# PK_MUV.net
KiCad netlist of a schematic drawn in EAGLE
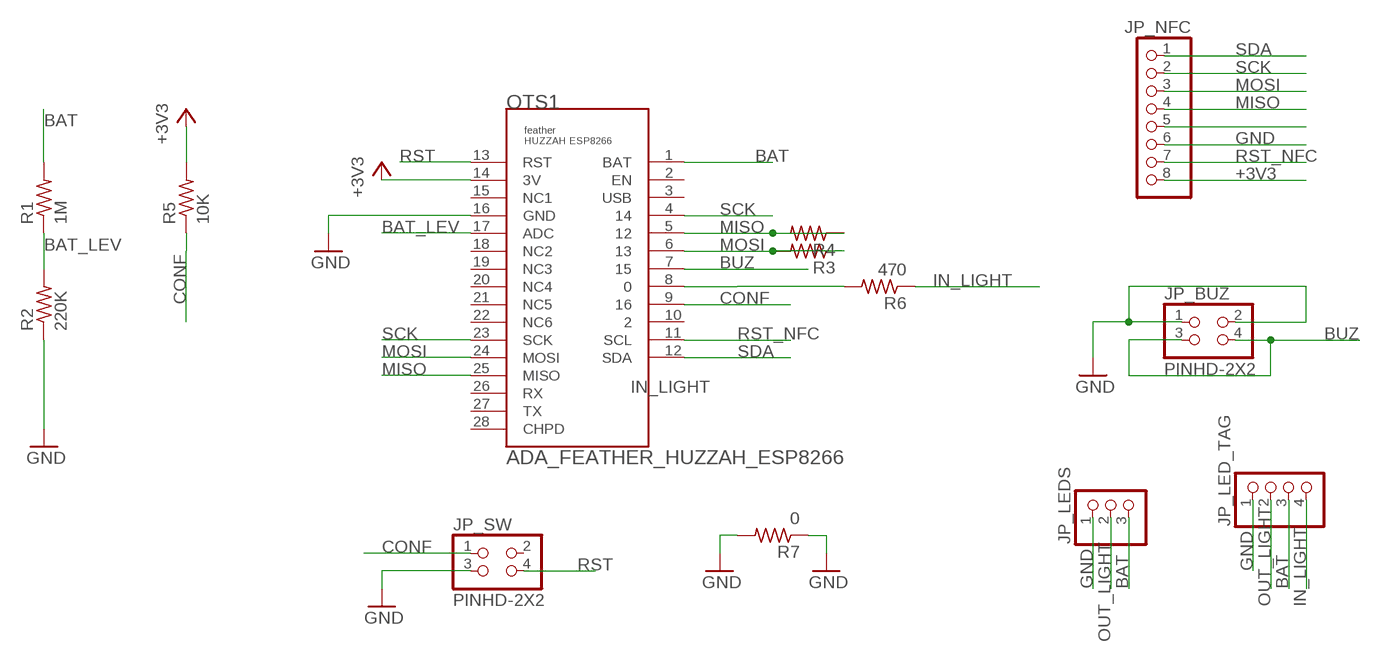
[diagram p0: schematic, sheet 1]

(export (version "E")
  (design (tool "Eeschema 10.0.6"))
  (components
    (comp (ref "JP_BUZ")
      (value "PINHD-2X2")
      (footprint "eagle-import:2X2")
      (libsource (lib "eagle-import") (part "PINHD-2X2"))
    )
    (comp (ref "JP_LEDS")
      (value "HEADER-1X3")
      (footprint "eagle-import:1X03_OVAL")
      (libsource (lib "eagle-import") (part "HEADER-1X3"))
    )
    (comp (ref "JP_LED_TAG")
      (value "HEADER-1X4")
      (footprint "eagle-import:1X04_OVAL")
      (libsource (lib "eagle-import") (part "HEADER-1X4"))
    )
    (comp (ref "JP_NFC")
      (value "HEADER-1X8")
      (footprint "eagle-import:1X08_OVAL")
      (libsource (lib "eagle-import") (part "HEADER-1X8"))
    )
    (comp (ref "JP_SW")
      (value "PINHD-2X2")
      (footprint "eagle-import:2X2")
      (libsource (lib "eagle-import") (part "PINHD-2X2"))
    )
    (comp (ref "OTS1")
      (value "ADA_FEATHER_HUZZAH_ESP8266")
      (footprint "eagle-import:ADA_FEATHER_HUZZAH_ESP8266")
      (libsource (lib "eagle-import") (part "ADA_FEATHER_HUZZAH_ESP8266"))
    )
    (comp (ref "R1")
      (value "1M")
      (footprint "eagle-import:M1206")
      (libsource (lib "eagle-import") (part "R-US_M1206"))
    )
    (comp (ref "R2")
      (value "220K")
      (footprint "eagle-import:M1206")
      (libsource (lib "eagle-import") (part "R-US_M1206"))
    )
    (comp (ref "R3")
      (value "R-US_M1206")
      (footprint "eagle-import:M1206")
      (libsource (lib "eagle-import") (part "R-US_M1206"))
    )
    (comp (ref "R4")
      (value "R-US_M1206")
      (footprint "eagle-import:M1206")
      (libsource (lib "eagle-import") (part "R-US_M1206"))
    )
    (comp (ref "R5")
      (value "10K")
      (footprint "eagle-import:M1206")
      (libsource (lib "eagle-import") (part "R-US_M1206"))
    )
    (comp (ref "R6")
      (value "470")
      (footprint "eagle-import:M1206")
      (libsource (lib "eagle-import") (part "R-US_M1206"))
    )
    (comp (ref "R7")
      (value "0")
      (footprint "eagle-import:M1206")
      (libsource (lib "eagle-import") (part "R-US_M1206"))
    )
  )
  (nets
    (net (code "1") (name "+3V3") (class "Default")
      (node (ref "JP_NFC") (pin "8") (pinfunction "8_8") (pintype "passive"))
      (node (ref "OTS1") (pin "14") (pinfunction "3V_14") (pintype "power_in"))
      (node (ref "R5") (pin "2") (pinfunction "2_2") (pintype "passive"))
    )
    (net (code "2") (name "/BAT") (class "Default")
      (node (ref "JP_LEDS") (pin "3") (pinfunction "3_3") (pintype "passive"))
      (node (ref "JP_LED_TAG") (pin "3") (pinfunction "3_3") (pintype "passive"))
      (node (ref "OTS1") (pin "1") (pinfunction "BAT_1") (pintype "power_in"))
      (node (ref "R1") (pin "2") (pinfunction "2_2") (pintype "passive"))
    )
    (net (code "3") (name "/BAT_LEV") (class "Default")
      (node (ref "OTS1") (pin "17") (pinfunction "ADC_17") (pintype "bidirectional"))
      (node (ref "R1") (pin "1") (pinfunction "1_1") (pintype "passive"))
      (node (ref "R2") (pin "2") (pinfunction "2_2") (pintype "passive"))
    )
    (net (code "4") (name "/BUZ") (class "Default")
      (node (ref "JP_BUZ") (pin "3") (pinfunction "3_3") (pintype "passive"))
      (node (ref "JP_BUZ") (pin "4") (pinfunction "4_4") (pintype "passive"))
      (node (ref "OTS1") (pin "7") (pinfunction "15_7") (pintype "bidirectional"))
    )
    (net (code "5") (name "/CONF") (class "Default")
      (node (ref "JP_SW") (pin "1") (pinfunction "1_1") (pintype "passive"))
      (node (ref "OTS1") (pin "9") (pinfunction "16_9") (pintype "bidirectional"))
      (node (ref "R5") (pin "1") (pinfunction "1_1") (pintype "passive"))
    )
    (net (code "6") (name "/IN_LIGHT") (class "Default")
      (node (ref "JP_LED_TAG") (pin "4") (pinfunction "4_4") (pintype "passive"))
      (node (ref "R6") (pin "1") (pinfunction "1_1") (pintype "passive"))
    )
    (net (code "7") (name "/MISO") (class "Default")
      (node (ref "JP_NFC") (pin "4") (pinfunction "4_4") (pintype "passive"))
      (node (ref "OTS1") (pin "25") (pinfunction "MISO_25") (pintype "bidirectional"))
      (node (ref "OTS1") (pin "5") (pinfunction "12_5") (pintype "bidirectional"))
      (node (ref "R4") (pin "1") (pinfunction "1_1") (pintype "passive"))
      (node (ref "R4") (pin "2") (pinfunction "2_2") (pintype "passive"))
    )
    (net (code "8") (name "/MOSI") (class "Default")
      (node (ref "JP_NFC") (pin "3") (pinfunction "3_3") (pintype "passive"))
      (node (ref "OTS1") (pin "24") (pinfunction "MOSI_24") (pintype "bidirectional"))
      (node (ref "OTS1") (pin "6") (pinfunction "13_6") (pintype "bidirectional"))
      (node (ref "R3") (pin "1") (pinfunction "1_1") (pintype "passive"))
      (node (ref "R3") (pin "2") (pinfunction "2_2") (pintype "passive"))
    )
    (net (code "9") (name "/OUT_LIGHT") (class "Default")
      (node (ref "JP_LEDS") (pin "2") (pinfunction "2_2") (pintype "passive"))
      (node (ref "JP_LED_TAG") (pin "2") (pinfunction "2_2") (pintype "passive"))
    )
    (net (code "10") (name "/RST") (class "Default")
      (node (ref "JP_SW") (pin "4") (pinfunction "4_4") (pintype "passive"))
      (node (ref "OTS1") (pin "13") (pinfunction "RST_13") (pintype "bidirectional"))
    )
    (net (code "11") (name "/RST_NFC") (class "Default")
      (node (ref "JP_NFC") (pin "7") (pinfunction "7_7") (pintype "passive"))
      (node (ref "OTS1") (pin "11") (pinfunction "SCL_11") (pintype "bidirectional"))
    )
    (net (code "12") (name "/SCK") (class "Default")
      (node (ref "JP_NFC") (pin "2") (pinfunction "2_2") (pintype "passive"))
      (node (ref "OTS1") (pin "23") (pinfunction "SCK_23") (pintype "bidirectional"))
      (node (ref "OTS1") (pin "4") (pinfunction "14_4") (pintype "bidirectional"))
    )
    (net (code "13") (name "/SDA") (class "Default")
      (node (ref "JP_NFC") (pin "1") (pinfunction "1_1") (pintype "passive"))
      (node (ref "OTS1") (pin "12") (pinfunction "SDA_12") (pintype "bidirectional"))
    )
    (net (code "14") (name "/USB") (class "Default")
      (node (ref "OTS1") (pin "3") (pinfunction "USB_3") (pintype "power_in"))
    )
    (net (code "15") (name "GND") (class "Default")
      (node (ref "JP_BUZ") (pin "1") (pinfunction "1_1") (pintype "passive"))
      (node (ref "JP_BUZ") (pin "2") (pinfunction "2_2") (pintype "passive"))
      (node (ref "JP_LEDS") (pin "1") (pinfunction "1_1") (pintype "passive"))
      (node (ref "JP_LED_TAG") (pin "1") (pinfunction "1_1") (pintype "passive"))
      (node (ref "JP_NFC") (pin "6") (pinfunction "6_6") (pintype "passive"))
      (node (ref "JP_SW") (pin "3") (pinfunction "3_3") (pintype "passive"))
      (node (ref "OTS1") (pin "16") (pinfunction "GND_16") (pintype "power_in"))
      (node (ref "R2") (pin "1") (pinfunction "1_1") (pintype "passive"))
      (node (ref "R7") (pin "1") (pinfunction "1_1") (pintype "passive"))
      (node (ref "R7") (pin "2") (pinfunction "2_2") (pintype "passive"))
    )
    (net (code "16") (name "Net-(OTS1-0)") (class "Default")
      (node (ref "OTS1") (pin "8") (pinfunction "0_8") (pintype "bidirectional"))
      (node (ref "R6") (pin "2") (pinfunction "2_2") (pintype "passive"))
    )
    (net (code "17") (name "unconnected-(JP_NFC-Pad5)") (class "Default")
      (node (ref "JP_NFC") (pin "5") (pinfunction "5_5") (pintype "passive"))
    )
    (net (code "18") (name "unconnected-(JP_SW-Pad2)") (class "Default")
      (node (ref "JP_SW") (pin "2") (pinfunction "2_2") (pintype "passive"))
    )
    (net (code "19") (name "unconnected-(OTS1-2-Pad10)") (class "Default")
      (node (ref "OTS1") (pin "10") (pinfunction "2_10") (pintype "bidirectional"))
    )
    (net (code "20") (name "unconnected-(OTS1-CHPD-Pad28)") (class "Default")
      (node (ref "OTS1") (pin "28") (pinfunction "CHPD_28") (pintype "bidirectional"))
    )
    (net (code "21") (name "unconnected-(OTS1-EN-Pad2)") (class "Default")
      (node (ref "OTS1") (pin "2") (pinfunction "EN_2") (pintype "input"))
    )
    (net (code "22") (name "unconnected-(OTS1-NC1-Pad15)") (class "Default")
      (node (ref "OTS1") (pin "15") (pinfunction "NC1_15") (pintype "no_connect"))
    )
    (net (code "23") (name "unconnected-(OTS1-NC2-Pad18)") (class "Default")
      (node (ref "OTS1") (pin "18") (pinfunction "NC2_18") (pintype "bidirectional"))
    )
    (net (code "24") (name "unconnected-(OTS1-NC3-Pad19)") (class "Default")
      (node (ref "OTS1") (pin "19") (pinfunction "NC3_19") (pintype "no_connect"))
    )
    (net (code "25") (name "unconnected-(OTS1-NC4-Pad20)") (class "Default")
      (node (ref "OTS1") (pin "20") (pinfunction "NC4_20") (pintype "no_connect"))
    )
    (net (code "26") (name "unconnected-(OTS1-NC5-Pad21)") (class "Default")
      (node (ref "OTS1") (pin "21") (pinfunction "NC5_21") (pintype "no_connect"))
    )
    (net (code "27") (name "unconnected-(OTS1-NC6-Pad22)") (class "Default")
      (node (ref "OTS1") (pin "22") (pinfunction "NC6_22") (pintype "no_connect"))
    )
    (net (code "28") (name "unconnected-(OTS1-RX-Pad26)") (class "Default")
      (node (ref "OTS1") (pin "26") (pinfunction "RX_26") (pintype "input"))
    )
    (net (code "29") (name "unconnected-(OTS1-TX-Pad27)") (class "Default")
      (node (ref "OTS1") (pin "27") (pinfunction "TX_27") (pintype "output"))
    )
  )
)
